# MPU-9150-MS5611.net
KiCad netlist of a schematic drawn in EAGLE
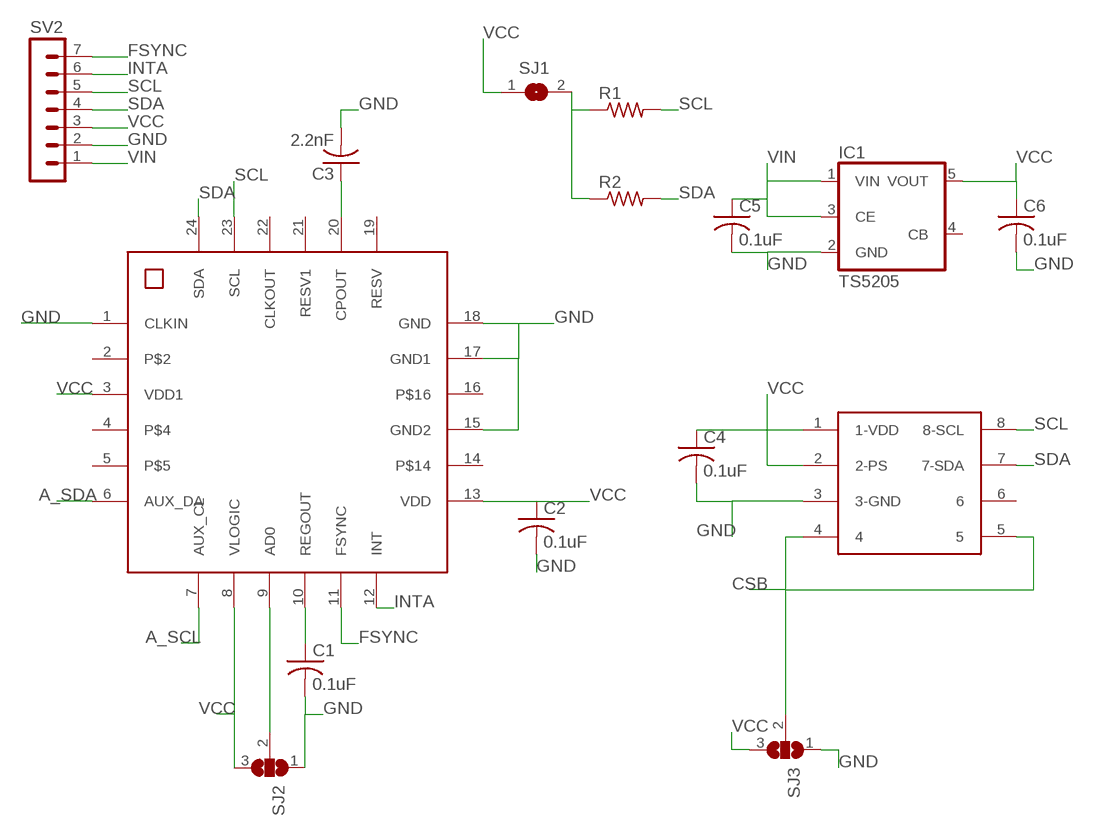
[diagram p0: schematic, sheet 1]

(export (version "E")
  (design (tool "Eeschema 10.0.6"))
  (components
    (comp (ref "C1")
      (value "0.1uF")
      (footprint "eagle-import:C0603")
      (libsource (lib "eagle-import") (part "C-USC0603"))
    )
    (comp (ref "C2")
      (value "0.1uF")
      (footprint "eagle-import:C0603")
      (libsource (lib "eagle-import") (part "C-USC0603"))
    )
    (comp (ref "C3")
      (value "2.2nF")
      (footprint "eagle-import:C0603")
      (libsource (lib "eagle-import") (part "C-USC0603"))
    )
    (comp (ref "C4")
      (value "0.1uF")
      (footprint "eagle-import:C0603")
      (libsource (lib "eagle-import") (part "C-USC0603"))
    )
    (comp (ref "C5")
      (value "0.1uF")
      (footprint "eagle-import:C0603")
      (libsource (lib "eagle-import") (part "C-USC0603"))
    )
    (comp (ref "C6")
      (value "0.1uF")
      (footprint "eagle-import:C0603")
      (libsource (lib "eagle-import") (part "C-USC0603"))
    )
    (comp (ref "IC1")
      (value "TS5205")
      (footprint "eagle-import:SOT25")
      (libsource (lib "eagle-import") (part "TS5205"))
    )
    (comp (ref "MPU-9150")
      (value "MPU-9150MPU-9150")
      (footprint "eagle-import:MPU-6050_QFN-24")
      (libsource (lib "eagle-import") (part "MPU-9150MPU-9150"))
    )
    (comp (ref "MS5611")
      (value "MS5611")
      (footprint "eagle-import:MS5611-PACKAGE")
      (libsource (lib "eagle-import") (part "MS5611"))
    )
    (comp (ref "R1")
      (value "R-US_R0603")
      (footprint "eagle-import:R0603")
      (libsource (lib "eagle-import") (part "R-US_R0603"))
    )
    (comp (ref "R2")
      (value "R-US_R0603")
      (footprint "eagle-import:R0603")
      (libsource (lib "eagle-import") (part "R-US_R0603"))
    )
    (comp (ref "SJ1") (value "SJ") (footprint "eagle-import:SJ") (libsource (lib "eagle-import") (part "SJ")))
    (comp (ref "SJ2")
      (value "SJ2W")
      (footprint "eagle-import:SJ_2")
      (libsource (lib "eagle-import") (part "SJ2W"))
    )
    (comp (ref "SJ3")
      (value "SJ2W")
      (footprint "eagle-import:SJ_2")
      (libsource (lib "eagle-import") (part "SJ2W"))
    )
    (comp (ref "SV2")
      (value "MA07-1")
      (footprint "eagle-import:MA07-1")
      (libsource (lib "eagle-import") (part "MA07-1"))
    )
  )
  (nets
    (net (code "1") (name "/A_SCL") (class "Default")
      (node (ref "MPU-9150") (pin "7") (pinfunction "AUX_CL_7") (pintype "bidirectional"))
    )
    (net (code "2") (name "/A_SDA") (class "Default")
      (node (ref "MPU-9150") (pin "6") (pinfunction "AUX_DA_6") (pintype "bidirectional"))
    )
    (net (code "3") (name "/CSB") (class "Default")
      (node (ref "MS5611") (pin "4") (pinfunction "4_4") (pintype "bidirectional"))
      (node (ref "MS5611") (pin "5") (pinfunction "5_5") (pintype "bidirectional"))
      (node (ref "SJ3") (pin "2") (pinfunction "2_2") (pintype "passive"))
    )
    (net (code "4") (name "/FSYNC") (class "Default")
      (node (ref "MPU-9150") (pin "11") (pinfunction "FSYNC_11") (pintype "bidirectional"))
      (node (ref "SV2") (pin "7") (pinfunction "7_7") (pintype "passive"))
    )
    (net (code "5") (name "/GND") (class "Default")
      (node (ref "C1") (pin "2") (pinfunction "2_2") (pintype "passive"))
      (node (ref "C2") (pin "2") (pinfunction "2_2") (pintype "passive"))
      (node (ref "C3") (pin "2") (pinfunction "2_2") (pintype "passive"))
      (node (ref "C4") (pin "2") (pinfunction "2_2") (pintype "passive"))
      (node (ref "C5") (pin "2") (pinfunction "2_2") (pintype "passive"))
      (node (ref "C6") (pin "2") (pinfunction "2_2") (pintype "passive"))
      (node (ref "IC1") (pin "2") (pinfunction "GND_2") (pintype "passive"))
      (node (ref "MPU-9150") (pin "1") (pinfunction "CLKIN_1") (pintype "bidirectional"))
      (node (ref "MPU-9150") (pin "15") (pinfunction "GND2_15") (pintype "bidirectional"))
      (node (ref "MPU-9150") (pin "17") (pinfunction "GND1_17") (pintype "bidirectional"))
      (node (ref "MPU-9150") (pin "18") (pinfunction "GND_18") (pintype "bidirectional"))
      (node (ref "MS5611") (pin "3") (pinfunction "3-GND_3") (pintype "bidirectional"))
      (node (ref "SJ2") (pin "1") (pinfunction "1_1") (pintype "passive"))
      (node (ref "SJ3") (pin "1") (pinfunction "1_1") (pintype "passive"))
      (node (ref "SV2") (pin "2") (pinfunction "2_2") (pintype "passive"))
    )
    (net (code "6") (name "/INTA") (class "Default")
      (node (ref "MPU-9150") (pin "12") (pinfunction "INT_12") (pintype "bidirectional"))
      (node (ref "SV2") (pin "6") (pinfunction "6_6") (pintype "passive"))
    )
    (net (code "7") (name "/SCL") (class "Default")
      (node (ref "MPU-9150") (pin "23") (pinfunction "SCL_23") (pintype "bidirectional"))
      (node (ref "MS5611") (pin "8") (pinfunction "8-SCL_8") (pintype "bidirectional"))
      (node (ref "R1") (pin "2") (pinfunction "2_2") (pintype "passive"))
      (node (ref "SV2") (pin "5") (pinfunction "5_5") (pintype "passive"))
    )
    (net (code "8") (name "/SDA") (class "Default")
      (node (ref "MPU-9150") (pin "24") (pinfunction "SDA_24") (pintype "bidirectional"))
      (node (ref "MS5611") (pin "7") (pinfunction "7-SDA_7") (pintype "bidirectional"))
      (node (ref "R2") (pin "2") (pinfunction "2_2") (pintype "passive"))
      (node (ref "SV2") (pin "4") (pinfunction "4_4") (pintype "passive"))
    )
    (net (code "9") (name "/VCC") (class "Default")
      (node (ref "C2") (pin "1") (pinfunction "1_1") (pintype "passive"))
      (node (ref "C4") (pin "1") (pinfunction "1_1") (pintype "passive"))
      (node (ref "C6") (pin "1") (pinfunction "1_1") (pintype "passive"))
      (node (ref "IC1") (pin "5") (pinfunction "VOUT_5") (pintype "passive"))
      (node (ref "MPU-9150") (pin "13") (pinfunction "VDD_13") (pintype "bidirectional"))
      (node (ref "MPU-9150") (pin "3") (pinfunction "VDD1_3") (pintype "bidirectional"))
      (node (ref "MPU-9150") (pin "8") (pinfunction "VLOGIC_8") (pintype "bidirectional"))
      (node (ref "MS5611") (pin "1") (pinfunction "1-VDD_1") (pintype "bidirectional"))
      (node (ref "MS5611") (pin "2") (pinfunction "2-PS_2") (pintype "bidirectional"))
      (node (ref "SJ1") (pin "1") (pinfunction "1_1") (pintype "passive"))
      (node (ref "SJ2") (pin "3") (pinfunction "3_3") (pintype "passive"))
      (node (ref "SJ3") (pin "3") (pinfunction "3_3") (pintype "passive"))
      (node (ref "SV2") (pin "3") (pinfunction "3_3") (pintype "passive"))
    )
    (net (code "10") (name "/VIN") (class "Default")
      (node (ref "C5") (pin "1") (pinfunction "1_1") (pintype "passive"))
      (node (ref "IC1") (pin "1") (pinfunction "VIN_1") (pintype "input"))
      (node (ref "IC1") (pin "3") (pinfunction "CE_3") (pintype "input"))
      (node (ref "SV2") (pin "1") (pinfunction "1_1") (pintype "passive"))
    )
    (net (code "11") (name "Net-(MPU-9150-AD0)") (class "Default")
      (node (ref "MPU-9150") (pin "9") (pinfunction "AD0_9") (pintype "bidirectional"))
      (node (ref "SJ2") (pin "2") (pinfunction "2_2") (pintype "passive"))
    )
    (net (code "12") (name "Net-(MPU-9150-CPOUT)") (class "Default")
      (node (ref "C3") (pin "1") (pinfunction "1_1") (pintype "passive"))
      (node (ref "MPU-9150") (pin "20") (pinfunction "CPOUT_20") (pintype "bidirectional"))
    )
    (net (code "13") (name "Net-(MPU-9150-REGOUT)") (class "Default")
      (node (ref "C1") (pin "1") (pinfunction "1_1") (pintype "passive"))
      (node (ref "MPU-9150") (pin "10") (pinfunction "REGOUT_10") (pintype "bidirectional"))
    )
    (net (code "14") (name "Net-(R1-Pad1)") (class "Default")
      (node (ref "R1") (pin "1") (pinfunction "1_1") (pintype "passive"))
      (node (ref "R2") (pin "1") (pinfunction "1_1") (pintype "passive"))
      (node (ref "SJ1") (pin "2") (pinfunction "2_2") (pintype "passive"))
    )
    (net (code "15") (name "unconnected-(IC1-CB-Pad4)") (class "Default")
      (node (ref "IC1") (pin "4") (pinfunction "CB_4") (pintype "input"))
    )
    (net (code "16") (name "unconnected-(MPU-9150-CLKOUT-Pad22)") (class "Default")
      (node (ref "MPU-9150") (pin "22") (pinfunction "CLKOUT_22") (pintype "bidirectional"))
    )
    (net (code "17") (name "unconnected-(MPU-9150-P$2-Pad2)") (class "Default")
      (node (ref "MPU-9150") (pin "2") (pinfunction "P$2_2") (pintype "bidirectional"))
    )
    (net (code "18") (name "unconnected-(MPU-9150-P$4-Pad4)") (class "Default")
      (node (ref "MPU-9150") (pin "4") (pinfunction "P$4_4") (pintype "bidirectional"))
    )
    (net (code "19") (name "unconnected-(MPU-9150-P$5-Pad5)") (class "Default")
      (node (ref "MPU-9150") (pin "5") (pinfunction "P$5_5") (pintype "bidirectional"))
    )
    (net (code "20") (name "unconnected-(MPU-9150-P$14-Pad14)") (class "Default")
      (node (ref "MPU-9150") (pin "14") (pinfunction "P$14_14") (pintype "bidirectional"))
    )
    (net (code "21") (name "unconnected-(MPU-9150-P$16-Pad16)") (class "Default")
      (node (ref "MPU-9150") (pin "16") (pinfunction "P$16_16") (pintype "bidirectional"))
    )
    (net (code "22") (name "unconnected-(MPU-9150-RESV-Pad19)") (class "Default")
      (node (ref "MPU-9150") (pin "19") (pinfunction "RESV_19") (pintype "bidirectional"))
    )
    (net (code "23") (name "unconnected-(MPU-9150-RESV1-Pad21)") (class "Default")
      (node (ref "MPU-9150") (pin "21") (pinfunction "RESV1_21") (pintype "bidirectional"))
    )
    (net (code "24") (name "unconnected-(MS5611-Pad6)") (class "Default")
      (node (ref "MS5611") (pin "6") (pinfunction "6_6") (pintype "bidirectional"))
    )
  )
)
